# Revised.net
KiCad netlist of a schematic drawn in EAGLE
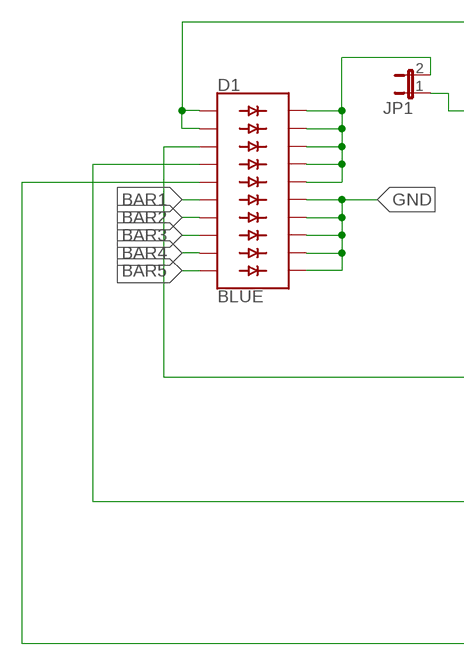
[diagram p0: schematic, sheet 1, part 1 of 2]
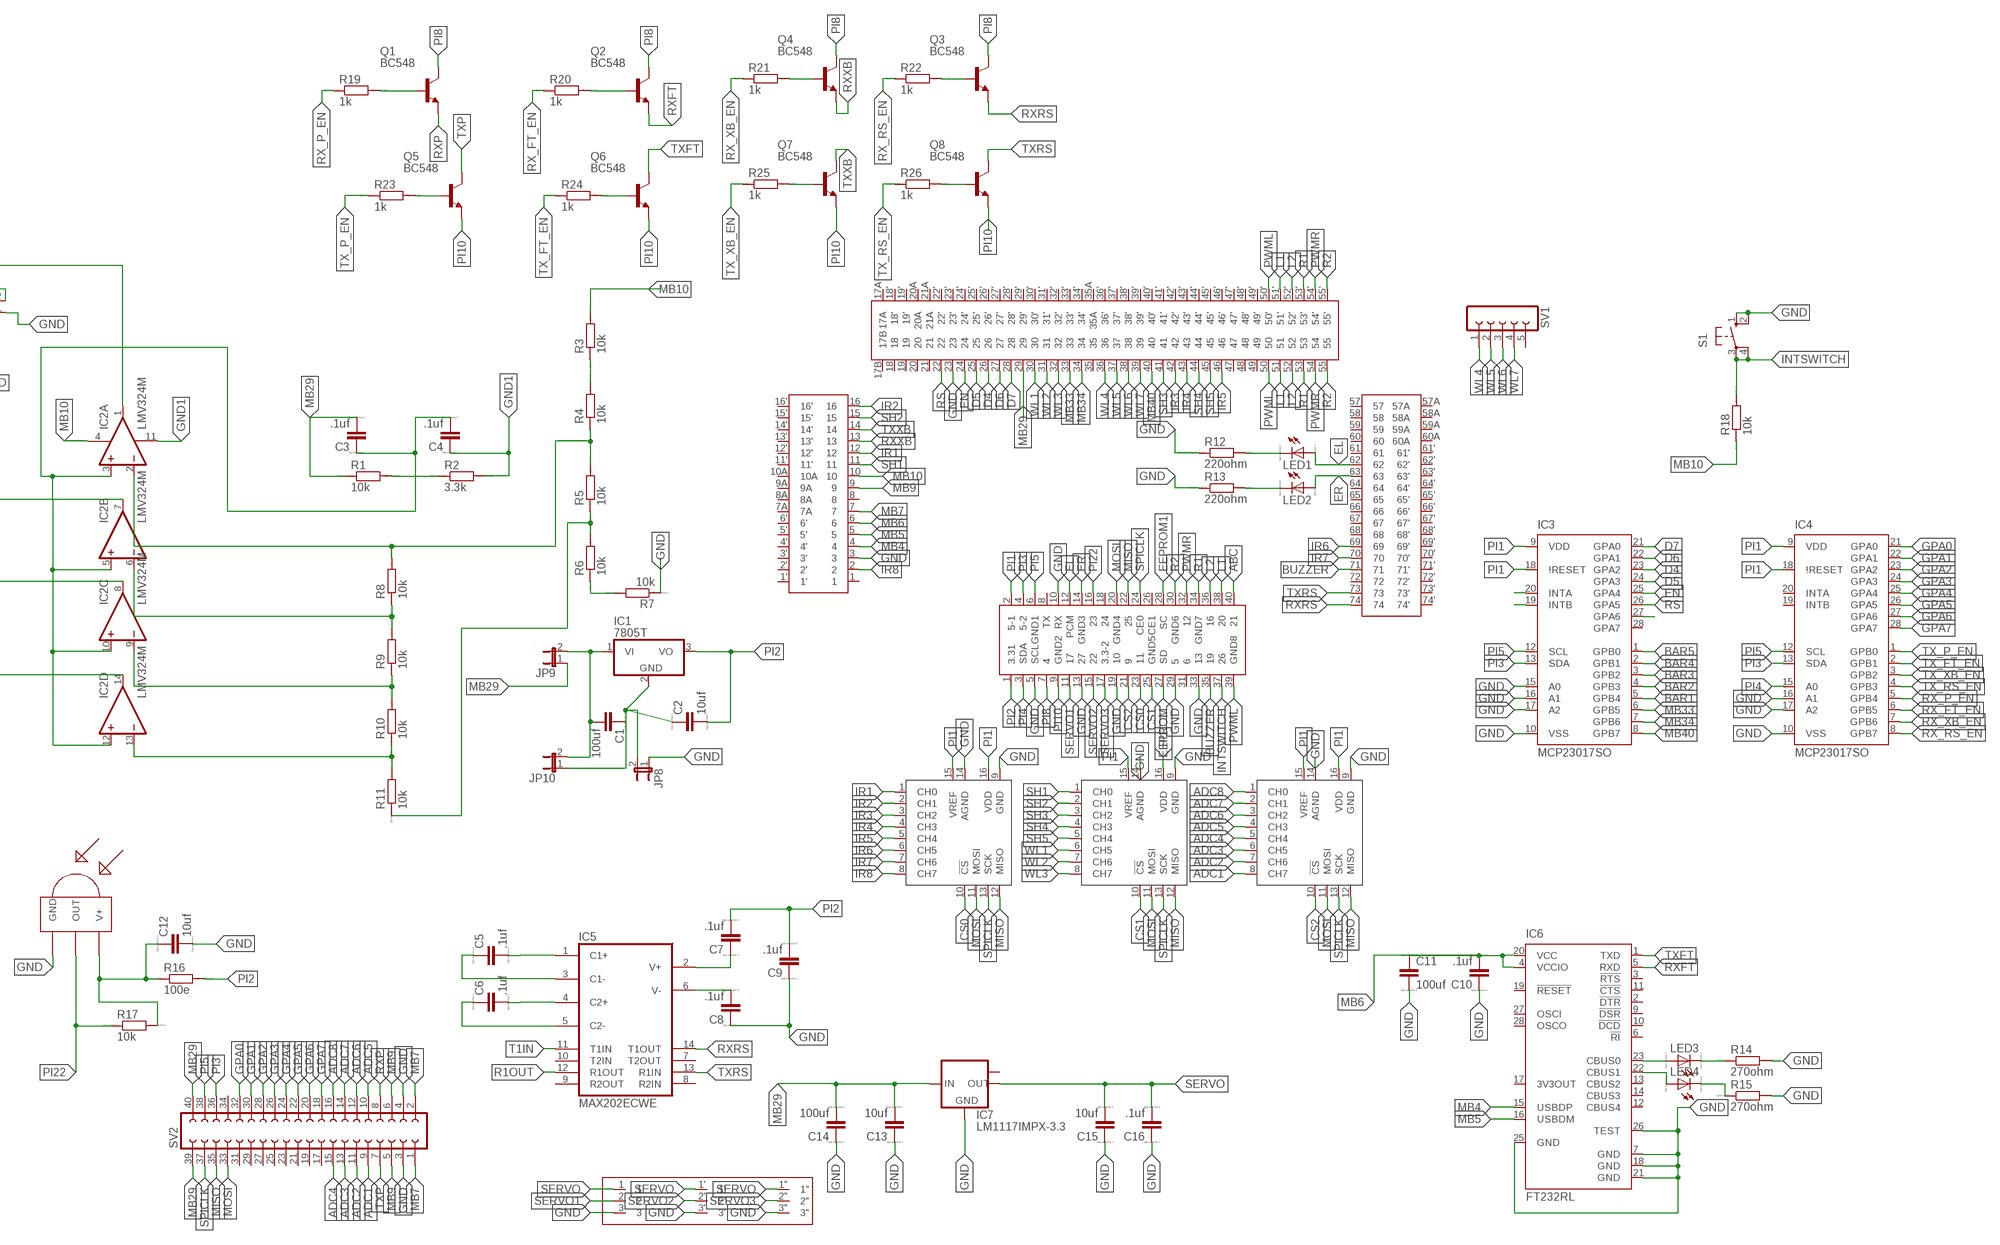
[diagram p1: schematic, sheet 1, part 2 of 2]

(export (version "E")
  (design (tool "Eeschema 10.0.6"))
  (components
    (comp (ref "C1")
      (value "100uf")
      (footprint "eagle-import:C1206")
      (libsource (lib "eagle-import") (part "CC1206"))
    )
    (comp (ref "C2")
      (value "10uf")
      (footprint "eagle-import:C1206")
      (libsource (lib "eagle-import") (part "CC1206"))
    )
    (comp (ref "C3")
      (value ".1uf")
      (footprint "eagle-import:C1206")
      (libsource (lib "eagle-import") (part "CC1206"))
    )
    (comp (ref "C4")
      (value ".1uf")
      (footprint "eagle-import:C1206")
      (libsource (lib "eagle-import") (part "CC1206"))
    )
    (comp (ref "C5")
      (value ".1uf")
      (footprint "eagle-import:C1206")
      (libsource (lib "eagle-import") (part "CC1206"))
    )
    (comp (ref "C6")
      (value ".1uf")
      (footprint "eagle-import:C1206")
      (libsource (lib "eagle-import") (part "CC1206"))
    )
    (comp (ref "C7")
      (value ".1uf")
      (footprint "eagle-import:C1206")
      (libsource (lib "eagle-import") (part "CC1206"))
    )
    (comp (ref "C8")
      (value ".1uf")
      (footprint "eagle-import:C1206")
      (libsource (lib "eagle-import") (part "CC1206"))
    )
    (comp (ref "C9")
      (value ".1uf")
      (footprint "eagle-import:C1206")
      (libsource (lib "eagle-import") (part "CC1206"))
    )
    (comp (ref "C10")
      (value ".1uf")
      (footprint "eagle-import:C1206")
      (libsource (lib "eagle-import") (part "CC1206"))
    )
    (comp (ref "C11")
      (value "100uf")
      (footprint "eagle-import:C1206")
      (libsource (lib "eagle-import") (part "CC1206"))
    )
    (comp (ref "C12")
      (value "10uf")
      (footprint "eagle-import:C1206")
      (libsource (lib "eagle-import") (part "CC1206"))
    )
    (comp (ref "C13")
      (value "10uf")
      (footprint "eagle-import:C1206")
      (libsource (lib "eagle-import") (part "CC1206"))
    )
    (comp (ref "C14")
      (value "100uf")
      (footprint "eagle-import:C1206")
      (libsource (lib "eagle-import") (part "CC1206"))
    )
    (comp (ref "C15")
      (value "10uf")
      (footprint "eagle-import:C1206")
      (libsource (lib "eagle-import") (part "CC1206"))
    )
    (comp (ref "C16")
      (value ".1uf")
      (footprint "eagle-import:C1206")
      (libsource (lib "eagle-import") (part "CC1206"))
    )
    (comp (ref "D1")
      (value "BLUE")
      (footprint "eagle-import:LED_BARGRAPH_10")
      (libsource (lib "eagle-import") (part "LED_BARGRAPH_10BLUE"))
    )
    (comp (ref "IC1")
      (value "7805T")
      (footprint "eagle-import:TO220H")
      (libsource (lib "eagle-import") (part "78T05"))
    )
    (comp (ref "IC2")
      (value "LMV324M")
      (footprint "eagle-import:SO14")
      (libsource (lib "eagle-import") (part "LMV324?M"))
    )
    (comp (ref "IC3")
      (value "MCP23017SO")
      (footprint "eagle-import:SO28W")
      (libsource (lib "eagle-import") (part "MCP23017SO"))
    )
    (comp (ref "IC4")
      (value "MCP23017SO")
      (footprint "eagle-import:SO28W")
      (libsource (lib "eagle-import") (part "MCP23017SO"))
    )
    (comp (ref "IC5")
      (value "MAX202ECWE")
      (footprint "eagle-import:SO16L")
      (fields (field (name "MPN") "MAX202ECWE+T"))
      (libsource (lib "eagle-import") (part "MAX202ECWE"))
    )
    (comp (ref "IC6")
      (value "FT232RL")
      (footprint "eagle-import:SSOP28")
      (libsource (lib "eagle-import") (part "FT232RL"))
    )
    (comp (ref "IC7")
      (value "LM1117IMPX-3.3")
      (footprint "eagle-import:SOT223")
      (libsource (lib "eagle-import") (part "LM1117IMPX-3.3"))
    )
    (comp (ref "JP1")
      (value "JP1E")
      (footprint "eagle-import:JP1")
      (libsource (lib "eagle-import") (part "JP1E"))
    )
    (comp (ref "JP8")
      (value "JP1E")
      (footprint "eagle-import:JP1")
      (libsource (lib "eagle-import") (part "JP1E"))
    )
    (comp (ref "JP9")
      (value "JP1E")
      (footprint "eagle-import:JP1")
      (libsource (lib "eagle-import") (part "JP1E"))
    )
    (comp (ref "JP10")
      (value "JP1E")
      (footprint "eagle-import:JP1")
      (libsource (lib "eagle-import") (part "JP1E"))
    )
    (comp (ref "LED1")
      (value "LED_E")
      (footprint "eagle-import:LED_1206")
      (libsource (lib "eagle-import") (part "LED_E"))
    )
    (comp (ref "LED2")
      (value "LED_E")
      (footprint "eagle-import:LED_1206")
      (libsource (lib "eagle-import") (part "LED_E"))
    )
    (comp (ref "LED3")
      (value "LED_E")
      (footprint "eagle-import:LED_1206")
      (libsource (lib "eagle-import") (part "LED_E"))
    )
    (comp (ref "LED4")
      (value "LED_E")
      (footprint "eagle-import:LED_1206")
      (libsource (lib "eagle-import") (part "LED_E"))
    )
    (comp (ref "Q1")
      (value "BC548")
      (footprint "eagle-import:TO92-EBC")
      (libsource (lib "eagle-import") (part "BC548"))
    )
    (comp (ref "Q2")
      (value "BC548")
      (footprint "eagle-import:TO92-EBC")
      (libsource (lib "eagle-import") (part "BC548"))
    )
    (comp (ref "Q3")
      (value "BC548")
      (footprint "eagle-import:TO92-EBC")
      (libsource (lib "eagle-import") (part "BC548"))
    )
    (comp (ref "Q4")
      (value "BC548")
      (footprint "eagle-import:TO92-EBC")
      (libsource (lib "eagle-import") (part "BC548"))
    )
    (comp (ref "Q5")
      (value "BC548")
      (footprint "eagle-import:TO92-EBC")
      (libsource (lib "eagle-import") (part "BC548"))
    )
    (comp (ref "Q6")
      (value "BC548")
      (footprint "eagle-import:TO92-EBC")
      (libsource (lib "eagle-import") (part "BC548"))
    )
    (comp (ref "Q7")
      (value "BC548")
      (footprint "eagle-import:TO92-EBC")
      (libsource (lib "eagle-import") (part "BC548"))
    )
    (comp (ref "Q8")
      (value "BC548")
      (footprint "eagle-import:TO92-EBC")
      (libsource (lib "eagle-import") (part "BC548"))
    )
    (comp (ref "R1")
      (value "10k")
      (footprint "eagle-import:R1206")
      (libsource (lib "eagle-import") (part "RR1206"))
    )
    (comp (ref "R2")
      (value "3.3k")
      (footprint "eagle-import:R1206")
      (libsource (lib "eagle-import") (part "RR1206"))
    )
    (comp (ref "R3")
      (value "10k")
      (footprint "eagle-import:R1206")
      (libsource (lib "eagle-import") (part "RR1206"))
    )
    (comp (ref "R4")
      (value "10k")
      (footprint "eagle-import:R1206")
      (libsource (lib "eagle-import") (part "RR1206"))
    )
    (comp (ref "R5")
      (value "10k")
      (footprint "eagle-import:R1206")
      (libsource (lib "eagle-import") (part "RR1206"))
    )
    (comp (ref "R6")
      (value "10k")
      (footprint "eagle-import:R1206")
      (libsource (lib "eagle-import") (part "RR1206"))
    )
    (comp (ref "R7")
      (value "10k")
      (footprint "eagle-import:R1206")
      (libsource (lib "eagle-import") (part "RR1206"))
    )
    (comp (ref "R8")
      (value "10k")
      (footprint "eagle-import:R1206")
      (libsource (lib "eagle-import") (part "RR1206"))
    )
    (comp (ref "R9")
      (value "10k")
      (footprint "eagle-import:R1206")
      (libsource (lib "eagle-import") (part "RR1206"))
    )
    (comp (ref "R10")
      (value "10k")
      (footprint "eagle-import:R1206")
      (libsource (lib "eagle-import") (part "RR1206"))
    )
    (comp (ref "R11")
      (value "10k")
      (footprint "eagle-import:R1206")
      (libsource (lib "eagle-import") (part "RR1206"))
    )
    (comp (ref "R12")
      (value "220ohm")
      (footprint "eagle-import:R1206")
      (libsource (lib "eagle-import") (part "RR1206"))
    )
    (comp (ref "R13")
      (value "220ohm")
      (footprint "eagle-import:R1206")
      (libsource (lib "eagle-import") (part "RR1206"))
    )
    (comp (ref "R14")
      (value "270ohm")
      (footprint "eagle-import:R1206")
      (libsource (lib "eagle-import") (part "RR1206"))
    )
    (comp (ref "R15")
      (value "270ohm")
      (footprint "eagle-import:R1206")
      (libsource (lib "eagle-import") (part "RR1206"))
    )
    (comp (ref "R16")
      (value "100e")
      (footprint "eagle-import:R1206")
      (libsource (lib "eagle-import") (part "RR1206"))
    )
    (comp (ref "R17")
      (value "10k")
      (footprint "eagle-import:R1206")
      (libsource (lib "eagle-import") (part "RR1206"))
    )
    (comp (ref "R18")
      (value "10k")
      (footprint "eagle-import:R1206")
      (libsource (lib "eagle-import") (part "RR1206"))
    )
    (comp (ref "R19")
      (value "1k")
      (footprint "eagle-import:R1206")
      (libsource (lib "eagle-import") (part "RR1206"))
    )
    (comp (ref "R20")
      (value "1k")
      (footprint "eagle-import:R1206")
      (libsource (lib "eagle-import") (part "RR1206"))
    )
    (comp (ref "R21")
      (value "1k")
      (footprint "eagle-import:R1206")
      (libsource (lib "eagle-import") (part "RR1206"))
    )
    (comp (ref "R22")
      (value "1k")
      (footprint "eagle-import:R1206")
      (libsource (lib "eagle-import") (part "RR1206"))
    )
    (comp (ref "R23")
      (value "1k")
      (footprint "eagle-import:R1206")
      (libsource (lib "eagle-import") (part "RR1206"))
    )
    (comp (ref "R24")
      (value "1k")
      (footprint "eagle-import:R1206")
      (libsource (lib "eagle-import") (part "RR1206"))
    )
    (comp (ref "R25")
      (value "1k")
      (footprint "eagle-import:R1206")
      (libsource (lib "eagle-import") (part "RR1206"))
    )
    (comp (ref "R26")
      (value "1k")
      (footprint "eagle-import:R1206")
      (libsource (lib "eagle-import") (part "RR1206"))
    )
    (comp (ref "S1")
      (value "10-XX")
      (footprint "eagle-import:B3F-10XX")
      (fields (field (name "MPN") "B3F-1000"))
      (libsource (lib "eagle-import") (part "10-XX"))
    )
    (comp (ref "SV1")
      (value "FE05-1")
      (footprint "eagle-import:FE05-1")
      (libsource (lib "eagle-import") (part "FE05-1"))
    )
    (comp (ref "SV2")
      (value "FE20-2")
      (footprint "eagle-import:FE20-2")
      (libsource (lib "eagle-import") (part "FE20-2"))
    )
    (comp (ref "U$1")
      (value "DAUGHTERBOARDDAUGHTERBOARD")
      (footprint "eagle-import:DAUGHTERBOARD")
      (libsource (lib "eagle-import") (part "DAUGHTERBOARDDAUGHTERBOARD"))
    )
    (comp (ref "U$2")
      (value "MALE_HEADER")
      (footprint "eagle-import:MALE_HEADER_PACKAGE")
      (libsource (lib "eagle-import") (part "MALE_HEADER"))
    )
    (comp (ref "U$3")
      (value "MCP3008SL")
      (footprint "eagle-import:SO16")
      (libsource (lib "eagle-import") (part "MCP3008SL"))
    )
    (comp (ref "U$4")
      (value "MCP3008SL")
      (footprint "eagle-import:SO16")
      (libsource (lib "eagle-import") (part "MCP3008SL"))
    )
    (comp (ref "U$5")
      (value "MCP3008SL")
      (footprint "eagle-import:SO16")
      (libsource (lib "eagle-import") (part "MCP3008SL"))
    )
    (comp (ref "U$6")
      (value "TSOP1738")
      (footprint "eagle-import:TSOP17XX")
      (libsource (lib "eagle-import") (part "TSOP1738"))
    )
    (comp (ref "U$7")
      (value "SERVO")
      (footprint "eagle-import:SERVO")
      (libsource (lib "eagle-import") (part "SERVO"))
    )
  )
  (nets
    (net (code "1") (name "ABC") (class "Default")
      (node (ref "U$2") (pin "40") (pinfunction "21_40") (pintype "bidirectional"))
    )
    (net (code "2") (name "ADC1") (class "Default")
      (node (ref "SV2") (pin "9") (pinfunction "9_9") (pintype "passive"))
      (node (ref "U$5") (pin "8") (pinfunction "CH7_8") (pintype "input"))
    )
    (net (code "3") (name "ADC2") (class "Default")
      (node (ref "SV2") (pin "11") (pinfunction "11_11") (pintype "passive"))
      (node (ref "U$5") (pin "7") (pinfunction "CH6_7") (pintype "input"))
    )
    (net (code "4") (name "ADC3") (class "Default")
      (node (ref "SV2") (pin "13") (pinfunction "13_13") (pintype "passive"))
      (node (ref "U$5") (pin "6") (pinfunction "CH5_6") (pintype "input"))
    )
    (net (code "5") (name "ADC4") (class "Default")
      (node (ref "SV2") (pin "15") (pinfunction "15_15") (pintype "passive"))
      (node (ref "U$5") (pin "5") (pinfunction "CH4_5") (pintype "input"))
    )
    (net (code "6") (name "ADC5") (class "Default")
      (node (ref "SV2") (pin "10") (pinfunction "10_10") (pintype "passive"))
      (node (ref "U$5") (pin "4") (pinfunction "CH3_4") (pintype "input"))
    )
    (net (code "7") (name "ADC6") (class "Default")
      (node (ref "SV2") (pin "12") (pinfunction "12_12") (pintype "passive"))
      (node (ref "U$5") (pin "3") (pinfunction "CH2_3") (pintype "input"))
    )
    (net (code "8") (name "ADC7") (class "Default")
      (node (ref "SV2") (pin "14") (pinfunction "14_14") (pintype "passive"))
      (node (ref "U$5") (pin "2") (pinfunction "CH1_2") (pintype "input"))
    )
    (net (code "9") (name "ADC8") (class "Default")
      (node (ref "SV2") (pin "16") (pinfunction "16_16") (pintype "passive"))
      (node (ref "U$5") (pin "1") (pinfunction "CH0_1") (pintype "input"))
    )
    (net (code "10") (name "BAR1") (class "Default")
      (node (ref "D1") (pin "6") (pinfunction "A5_6") (pintype "passive"))
      (node (ref "IC3") (pin "5") (pinfunction "GPB4_5") (pintype "bidirectional"))
    )
    (net (code "11") (name "BAR2") (class "Default")
      (node (ref "D1") (pin "7") (pinfunction "A6_7") (pintype "passive"))
      (node (ref "IC3") (pin "4") (pinfunction "GPB3_4") (pintype "bidirectional"))
    )
    (net (code "12") (name "BAR3") (class "Default")
      (node (ref "D1") (pin "8") (pinfunction "A7_8") (pintype "passive"))
      (node (ref "IC3") (pin "3") (pinfunction "GPB2_3") (pintype "bidirectional"))
    )
    (net (code "13") (name "BAR4") (class "Default")
      (node (ref "D1") (pin "9") (pinfunction "A8_9") (pintype "passive"))
      (node (ref "IC3") (pin "2") (pinfunction "GPB1_2") (pintype "bidirectional"))
    )
    (net (code "14") (name "BAR5") (class "Default")
      (node (ref "D1") (pin "10") (pinfunction "A9_10") (pintype "passive"))
      (node (ref "IC3") (pin "1") (pinfunction "GPB0_1") (pintype "bidirectional"))
    )
    (net (code "15") (name "BUZZER") (class "Default")
      (node (ref "U$1") (pin "71") (pinfunction "71_71") (pintype "output"))
      (node (ref "U$2") (pin "35") (pinfunction "19_35") (pintype "bidirectional"))
    )
    (net (code "16") (name "CS0") (class "Default")
      (node (ref "U$2") (pin "23") (pinfunction "11_23") (pintype "bidirectional"))
      (node (ref "U$3") (pin "10") (pinfunction "~{CS}_10") (pintype "input"))
    )
    (net (code "17") (name "CS1") (class "Default")
      (node (ref "U$2") (pin "25") (pinfunction "GND5_25") (pintype "bidirectional"))
      (node (ref "U$4") (pin "10") (pinfunction "~{CS}_10") (pintype "input"))
    )
    (net (code "18") (name "CS2") (class "Default")
      (node (ref "U$2") (pin "21") (pinfunction "9_21") (pintype "bidirectional"))
      (node (ref "U$5") (pin "10") (pinfunction "~{CS}_10") (pintype "input"))
    )
    (net (code "19") (name "D4") (class "Default")
      (node (ref "IC3") (pin "23") (pinfunction "GPA2_23") (pintype "bidirectional"))
      (node (ref "U$1") (pin "26") (pinfunction "26_26") (pintype "output"))
    )
    (net (code "20") (name "D5") (class "Default")
      (node (ref "IC3") (pin "24") (pinfunction "GPA3_24") (pintype "bidirectional"))
      (node (ref "U$1") (pin "25") (pinfunction "25_25") (pintype "output"))
    )
    (net (code "21") (name "D6") (class "Default")
      (node (ref "IC3") (pin "22") (pinfunction "GPA1_22") (pintype "bidirectional"))
      (node (ref "U$1") (pin "27") (pinfunction "27_27") (pintype "output"))
    )
    (net (code "22") (name "D7") (class "Default")
      (node (ref "IC3") (pin "21") (pinfunction "GPA0_21") (pintype "bidirectional"))
      (node (ref "U$1") (pin "28") (pinfunction "28_28") (pintype "output"))
    )
    (net (code "23") (name "EEPROM") (class "Default")
      (node (ref "U$2") (pin "27") (pinfunction "SD_27") (pintype "bidirectional"))
    )
    (net (code "24") (name "EEPROM1") (class "Default")
      (node (ref "U$2") (pin "28") (pinfunction "SC_28") (pintype "bidirectional"))
    )
    (net (code "25") (name "EL") (class "Default")
      (node (ref "LED1") (pin "A") (pinfunction "A_A") (pintype "passive"))
      (node (ref "U$1") (pin "62") (pinfunction "62_62") (pintype "output"))
      (node (ref "U$2") (pin "12") (pinfunction "PCM_12") (pintype "bidirectional"))
    )
    (net (code "26") (name "EN") (class "Default")
      (node (ref "IC3") (pin "25") (pinfunction "GPA4_25") (pintype "bidirectional"))
      (node (ref "U$1") (pin "24") (pinfunction "24_24") (pintype "output"))
    )
    (net (code "27") (name "ER") (class "Default")
      (node (ref "LED2") (pin "A") (pinfunction "A_A") (pintype "passive"))
      (node (ref "U$1") (pin "63") (pinfunction "63_63") (pintype "output"))
      (node (ref "U$2") (pin "14") (pinfunction "GND3_14") (pintype "bidirectional"))
    )
    (net (code "28") (name "GND") (class "Default")
      (node (ref "C10") (pin "1") (pinfunction "1_1") (pintype "passive"))
      (node (ref "C11") (pin "2") (pinfunction "2_2") (pintype "passive"))
      (node (ref "C12") (pin "2") (pinfunction "2_2") (pintype "passive"))
      (node (ref "C13") (pin "1") (pinfunction "1_1") (pintype "passive"))
      (node (ref "C14") (pin "1") (pinfunction "1_1") (pintype "passive"))
      (node (ref "C15") (pin "1") (pinfunction "1_1") (pintype "passive"))
      (node (ref "C16") (pin "1") (pinfunction "1_1") (pintype "passive"))
      (node (ref "C8") (pin "1") (pinfunction "1_1") (pintype "passive"))
      (node (ref "C9") (pin "1") (pinfunction "1_1") (pintype "passive"))
      (node (ref "D1") (pin "11") (pinfunction "C9_11") (pintype "passive"))
      (node (ref "D1") (pin "12") (pinfunction "C8_12") (pintype "passive"))
      (node (ref "D1") (pin "13") (pinfunction "C7_13") (pintype "passive"))
      (node (ref "D1") (pin "14") (pinfunction "C6_14") (pintype "passive"))
      (node (ref "D1") (pin "15") (pinfunction "C5_15") (pintype "passive"))
      (node (ref "IC3") (pin "10") (pinfunction "VSS_10") (pintype "power_in"))
      (node (ref "IC3") (pin "15") (pinfunction "A0_15") (pintype "input"))
      (node (ref "IC3") (pin "16") (pinfunction "A1_16") (pintype "input"))
      (node (ref "IC3") (pin "17") (pinfunction "A2_17") (pintype "input"))
      (node (ref "IC4") (pin "10") (pinfunction "VSS_10") (pintype "power_in"))
      (node (ref "IC4") (pin "16") (pinfunction "A1_16") (pintype "input"))
      (node (ref "IC4") (pin "17") (pinfunction "A2_17") (pintype "input"))
      (node (ref "IC6") (pin "18") (pinfunction "GND_18") (pintype "power_in"))
      (node (ref "IC6") (pin "21") (pinfunction "GND_21") (pintype "power_in"))
      (node (ref "IC6") (pin "25") (pinfunction "GND_25") (pintype "power_in"))
      (node (ref "IC6") (pin "26") (pinfunction "TEST_26") (pintype "input"))
      (node (ref "IC6") (pin "7") (pinfunction "GND_7") (pintype "power_in"))
      (node (ref "IC7") (pin "1") (pinfunction "GND_1") (pintype "input"))
      (node (ref "JP1") (pin "1") (pinfunction "1_1") (pintype "passive"))
      (node (ref "JP8") (pin "1") (pinfunction "1_1") (pintype "passive"))
      (node (ref "R12") (pin "1") (pinfunction "1_1") (pintype "passive"))
      (node (ref "R13") (pin "1") (pinfunction "1_1") (pintype "passive"))
      (node (ref "R14") (pin "2") (pinfunction "2_2") (pintype "passive"))
      (node (ref "R15") (pin "2") (pinfunction "2_2") (pintype "passive"))
      (node (ref "R7") (pin "1") (pinfunction "1_1") (pintype "passive"))
      (node (ref "S1") (pin "1") (pinfunction "S_1") (pintype "passive"))
      (node (ref "S1") (pin "2") (pinfunction "S1_2") (pintype "passive"))
      (node (ref "SV2") (pin "3") (pinfunction "3_3") (pintype "passive"))
      (node (ref "SV2") (pin "4") (pinfunction "4_4") (pintype "passive"))
      (node (ref "U$1") (pin "23") (pinfunction "23_23") (pintype "output"))
      (node (ref "U$1") (pin "3") (pinfunction "3_3") (pintype "output"))
      (node (ref "U$2") (pin "10") (pinfunction "RX_10") (pintype "bidirectional"))
      (node (ref "U$2") (pin "13") (pinfunction "27_13") (pintype "bidirectional"))
      (node (ref "U$2") (pin "19") (pinfunction "10_19") (pintype "bidirectional"))
      (node (ref "U$2") (pin "29") (pinfunction "5_29") (pintype "bidirectional"))
      (node (ref "U$2") (pin "33") (pinfunction "13_33") (pintype "bidirectional"))
      (node (ref "U$2") (pin "5") (pinfunction "SCL_5") (pintype "bidirectional"))
      (node (ref "U$3") (pin "14") (pinfunction "AGND_14") (pintype "power_in"))
      (node (ref "U$3") (pin "9") (pinfunction "GND_9") (pintype "power_in"))
      (node (ref "U$4") (pin "14") (pinfunction "AGND_14") (pintype "power_in"))
      (node (ref "U$4") (pin "9") (pinfunction "GND_9") (pintype "power_in"))
      (node (ref "U$5") (pin "14") (pinfunction "AGND_14") (pintype "power_in"))
      (node (ref "U$5") (pin "9") (pinfunction "GND_9") (pintype "power_in"))
      (node (ref "U$6") (pin "GND") (pinfunction "GND_GND") (pintype "bidirectional"))
      (node (ref "U$7") (pin "3") (pinfunction "3_3") (pintype "bidirectional"))
      (node (ref "U$7") (pin "3\"") (pinfunction "3\"_3\"") (pintype "bidirectional"))
      (node (ref "U$7") (pin "3'") (pinfunction "3'_3'") (pintype "bidirectional"))
    )
    (net (code "29") (name "GND1") (class "Default")
      (node (ref "C4") (pin "1") (pinfunction "1_1") (pintype "passive"))
      (node (ref "IC2") (pin "11") (pinfunction "V-_11") (pintype "power_in"))
      (node (ref "R2") (pin "2") (pinfunction "2_2") (pintype "passive"))
    )
    (net (code "30") (name "GPA0") (class "Default")
      (node (ref "IC4") (pin "21") (pinfunction "GPA0_21") (pintype "bidirectional"))
      (node (ref "SV2") (pin "32") (pinfunction "32_32") (pintype "passive"))
    )
    (net (code "31") (name "GPA1") (class "Default")
      (node (ref "IC4") (pin "22") (pinfunction "GPA1_22") (pintype "bidirectional"))
      (node (ref "SV2") (pin "30") (pinfunction "30_30") (pintype "passive"))
    )
    (net (code "32") (name "GPA2") (class "Default")
      (node (ref "IC4") (pin "23") (pinfunction "GPA2_23") (pintype "bidirectional"))
      (node (ref "SV2") (pin "28") (pinfunction "28_28") (pintype "passive"))
    )
    (net (code "33") (name "GPA3") (class "Default")
      (node (ref "IC4") (pin "24") (pinfunction "GPA3_24") (pintype "bidirectional"))
      (node (ref "SV2") (pin "26") (pinfunction "26_26") (pintype "passive"))
    )
    (net (code "34") (name "GPA4") (class "Default")
      (node (ref "IC4") (pin "25") (pinfunction "GPA4_25") (pintype "bidirectional"))
      (node (ref "SV2") (pin "24") (pinfunction "24_24") (pintype "passive"))
    )
    (net (code "35") (name "GPA5") (class "Default")
      (node (ref "IC4") (pin "26") (pinfunction "GPA5_26") (pintype "bidirectional"))
      (node (ref "SV2") (pin "22") (pinfunction "22_22") (pintype "passive"))
    )
    (net (code "36") (name "GPA6") (class "Default")
      (node (ref "IC4") (pin "27") (pinfunction "GPA6_27") (pintype "bidirectional"))
      (node (ref "SV2") (pin "20") (pinfunction "20_20") (pintype "passive"))
    )
    (net (code "37") (name "GPA7") (class "Default")
      (node (ref "IC4") (pin "28") (pinfunction "GPA7_28") (pintype "bidirectional"))
      (node (ref "SV2") (pin "18") (pinfunction "18_18") (pintype "passive"))
    )
    (net (code "38") (name "INTSWITCH") (class "Default")
      (node (ref "R18") (pin "2") (pinfunction "2_2") (pintype "passive"))
      (node (ref "S1") (pin "3") (pinfunction "P_3") (pintype "passive"))
      (node (ref "S1") (pin "4") (pinfunction "P1_4") (pintype "passive"))
      (node (ref "U$2") (pin "37") (pinfunction "26_37") (pintype "bidirectional"))
    )
    (net (code "39") (name "IR1") (class "Default")
      (node (ref "U$1") (pin "12") (pinfunction "12_12") (pintype "output"))
      (node (ref "U$3") (pin "1") (pinfunction "CH0_1") (pintype "input"))
    )
    (net (code "40") (name "IR2") (class "Default")
      (node (ref "U$1") (pin "16") (pinfunction "16_16") (pintype "output"))
      (node (ref "U$3") (pin "2") (pinfunction "CH1_2") (pintype "input"))
    )
    (net (code "41") (name "IR3") (class "Default")
      (node (ref "U$1") (pin "42") (pinfunction "42_42") (pintype "output"))
      (node (ref "U$3") (pin "3") (pinfunction "CH2_3") (pintype "input"))
    )
    (net (code "42") (name "IR4") (class "Default")
      (node (ref "U$1") (pin "43") (pinfunction "43_43") (pintype "output"))
      (node (ref "U$3") (pin "4") (pinfunction "CH3_4") (pintype "input"))
    )
    (net (code "43") (name "IR5") (class "Default")
      (node (ref "U$1") (pin "46") (pinfunction "46_46") (pintype "output"))
      (node (ref "U$3") (pin "5") (pinfunction "CH4_5") (pintype "input"))
    )
    (net (code "44") (name "IR6") (class "Default")
      (node (ref "U$1") (pin "69") (pinfunction "69_69") (pintype "output"))
      (node (ref "U$3") (pin "6") (pinfunction "CH5_6") (pintype "input"))
    )
    (net (code "45") (name "IR7") (class "Default")
      (node (ref "U$1") (pin "70") (pinfunction "70_70") (pintype "output"))
      (node (ref "U$3") (pin "7") (pinfunction "CH6_7") (pintype "input"))
    )
    (net (code "46") (name "IR8") (class "Default")
      (node (ref "U$1") (pin "2") (pinfunction "2_2") (pintype "output"))
      (node (ref "U$3") (pin "8") (pinfunction "CH7_8") (pintype "input"))
    )
    (net (code "47") (name "L1") (class "Default")
      (node (ref "U$1") (pin "51") (pinfunction "51_51") (pintype "output"))
      (node (ref "U$1") (pin "51'") (pinfunction "51'_51'") (pintype "output"))
      (node (ref "U$2") (pin "38") (pinfunction "20_38") (pintype "bidirectional"))
    )
    (net (code "48") (name "L2") (class "Default")
      (node (ref "U$1") (pin "52") (pinfunction "52_52") (pintype "output"))
      (node (ref "U$1") (pin "52'") (pinfunction "52'_52'") (pintype "output"))
      (node (ref "U$2") (pin "36") (pinfunction "16_36") (pintype "bidirectional"))
    )
    (net (code "49") (name "MB4") (class "Default")
      (node (ref "IC6") (pin "15") (pinfunction "USBDP_15") (pintype "bidirectional"))
      (node (ref "U$1") (pin "4") (pinfunction "4_4") (pintype "output"))
    )
    (net (code "50") (name "MB5") (class "Default")
      (node (ref "IC6") (pin "16") (pinfunction "USBDM_16") (pintype "bidirectional"))
      (node (ref "U$1") (pin "5") (pinfunction "5_5") (pintype "output"))
    )
    (net (code "51") (name "MB6") (class "Default")
      (node (ref "C10") (pin "2") (pinfunction "2_2") (pintype "passive"))
      (node (ref "C11") (pin "1") (pinfunction "1_1") (pintype "passive"))
      (node (ref "IC6") (pin "20") (pinfunction "VCC_20") (pintype "power_in"))
      (node (ref "IC6") (pin "4") (pinfunction "VCCIO_4") (pintype "power_in"))
      (node (ref "U$1") (pin "6") (pinfunction "6_6") (pintype "output"))
    )
    (net (code "52") (name "MB7") (class "Default")
      (node (ref "SV2") (pin "1") (pinfunction "1_1") (pintype "passive"))
      (node (ref "SV2") (pin "2") (pinfunction "2_2") (pintype "passive"))
      (node (ref "U$1") (pin "7") (pinfunction "7_7") (pintype "output"))
    )
    (net (code "53") (name "MB9") (class "Default")
      (node (ref "SV2") (pin "5") (pinfunction "5_5") (pintype "passive"))
      (node (ref "SV2") (pin "6") (pinfunction "6_6") (pintype "passive"))
      (node (ref "U$1") (pin "9") (pinfunction "9_9") (pintype "output"))
    )
    (net (code "54") (name "MB10") (class "Default")
      (node (ref "IC2") (pin "4") (pinfunction "V+_4") (pintype "power_in"))
      (node (ref "R18") (pin "1") (pinfunction "1_1") (pintype "passive"))
      (node (ref "R3") (pin "2") (pinfunction "2_2") (pintype "passive"))
      (node (ref "U$1") (pin "10") (pinfunction "10_10") (pintype "output"))
    )
    (net (code "55") (name "MB29") (class "Default")
      (node (ref "C13") (pin "2") (pinfunction "2_2") (pintype "passive"))
      (node (ref "C14") (pin "2") (pinfunction "2_2") (pintype "passive"))
      (node (ref "C3") (pin "2") (pinfunction "2_2") (pintype "passive"))
      (node (ref "IC7") (pin "3") (pinfunction "IN_3") (pintype "input"))
      (node (ref "JP9") (pin "1") (pinfunction "1_1") (pintype "passive"))
      (node (ref "R1") (pin "1") (pinfunction "1_1") (pintype "passive"))
      (node (ref "SV2") (pin "39") (pinfunction "39_39") (pintype "passive"))
      (node (ref "SV2") (pin "40") (pinfunction "40_40") (pintype "passive"))
      (node (ref "U$1") (pin "29") (pinfunction "29_29") (pintype "output"))
    )
    (net (code "56") (name "MB33") (class "Default")
      (node (ref "IC3") (pin "6") (pinfunction "GPB5_6") (pintype "bidirectional"))
      (node (ref "U$1") (pin "33") (pinfunction "33_33") (pintype "output"))
    )
    (net (code "57") (name "MB34") (class "Default")
      (node (ref "IC3") (pin "7") (pinfunction "GPB6_7") (pintype "bidirectional"))
      (node (ref "U$1") (pin "34") (pinfunction "34_34") (pintype "output"))
    )
    (net (code "58") (name "MB40") (class "Default")
      (node (ref "IC3") (pin "8") (pinfunction "GPB7_8") (pintype "bidirectional"))
      (node (ref "U$1") (pin "40") (pinfunction "40_40") (pintype "output"))
    )
    (net (code "59") (name "MISO") (class "Default")
      (node (ref "SV2") (pin "35") (pinfunction "35_35") (pintype "passive"))
      (node (ref "U$2") (pin "22") (pinfunction "25_22") (pintype "bidirectional"))
      (node (ref "U$3") (pin "12") (pinfunction "MISO_12") (pintype "output"))
      (node (ref "U$4") (pin "12") (pinfunction "MISO_12") (pintype "output"))
      (node (ref "U$5") (pin "12") (pinfunction "MISO_12") (pintype "output"))
    )
    (net (code "60") (name "MOSI") (class "Default")
      (node (ref "SV2") (pin "33") (pinfunction "33_33") (pintype "passive"))
      (node (ref "U$2") (pin "20") (pinfunction "GND4_20") (pintype "bidirectional"))
      (node (ref "U$3") (pin "11") (pinfunction "MOSI_11") (pintype "input"))
      (node (ref "U$4") (pin "11") (pinfunction "MOSI_11") (pintype "input"))
      (node (ref "U$5") (pin "11") (pinfunction "MOSI_11") (pintype "input"))
    )
    (net (code "61") (name "Net-(C12-Pad1)") (class "Default")
      (node (ref "C12") (pin "1") (pinfunction "1_1") (pintype "passive"))
      (node (ref "R16") (pin "1") (pinfunction "1_1") (pintype "passive"))
      (node (ref "R17") (pin "2") (pinfunction "2_2") (pintype "passive"))
      (node (ref "U$6") (pin "V+") (pinfunction "V+_V+") (pintype "bidirectional"))
    )
    (net (code "62") (name "Net-(D1-A)") (class "Default")
      (node (ref "D1") (pin "1") (pinfunction "A_1") (pintype "passive"))
      (node (ref "D1") (pin "2") (pinfunction "A1_2") (pintype "passive"))
      (node (ref "IC2") (pin "1") (pinfunction "OUT_1") (pintype "output"))
    )
    (net (code "63") (name "Net-(D1-A2)") (class "Default")
      (node (ref "D1") (pin "3") (pinfunction "A2_3") (pintype "passive"))
      (node (ref "IC2") (pin "7") (pinfunction "OUT_7") (pintype "output"))
    )
    (net (code "64") (name "Net-(D1-A3)") (class "Default")
      (node (ref "D1") (pin "4") (pinfunction "A3_4") (pintype "passive"))
      (node (ref "IC2") (pin "8") (pinfunction "OUT_8") (pintype "output"))
    )
    (net (code "65") (name "Net-(D1-A4)") (class "Default")
      (node (ref "D1") (pin "5") (pinfunction "A4_5") (pintype "passive"))
      (node (ref "IC2") (pin "14") (pinfunction "OUT_14") (pintype "output"))
    )
    (net (code "66") (name "Net-(D1-C)") (class "Default")
      (node (ref "D1") (pin "16") (pinfunction "C4_16") (pintype "passive"))
      (node (ref "D1") (pin "17") (pinfunction "C3_17") (pintype "passive"))
      (node (ref "D1") (pin "18") (pinfunction "C2_18") (pintype "passive"))
      (node (ref "D1") (pin "19") (pinfunction "C1_19") (pintype "passive"))
      (node (ref "D1") (pin "20") (pinfunction "C_20") (pintype "passive"))
      (node (ref "JP1") (pin "2") (pinfunction "2_2") (pintype "passive"))
    )
    (net (code "67") (name "Net-(IC1-GND)") (class "Default")
      (node (ref "C1") (pin "1") (pinfunction "1_1") (pintype "passive"))
      (node (ref "C2") (pin "1") (pinfunction "1_1") (pintype "passive"))
      (node (ref "IC1") (pin "2") (pinfunction "GND_2") (pintype "passive"))
      (node (ref "JP10") (pin "1") (pinfunction "1_1") (pintype "passive"))
      (node (ref "JP8") (pin "2") (pinfunction "2_2") (pintype "passive"))
    )
    (net (code "68") (name "Net-(IC1-VI)") (class "Default")
      (node (ref "C1") (pin "2") (pinfunction "2_2") (pintype "passive"))
      (node (ref "IC1") (pin "1") (pinfunction "VI_1") (pintype "input"))
      (node (ref "JP10") (pin "2") (pinfunction "2_2") (pintype "passive"))
      (node (ref "JP9") (pin "2") (pinfunction "2_2") (pintype "passive"))
    )
    (net (code "69") (name "Net-(IC2A-+IN)") (class "Default")
      (node (ref "C3") (pin "1") (pinfunction "1_1") (pintype "passive"))
      (node (ref "C4") (pin "2") (pinfunction "2_2") (pintype "passive"))
      (node (ref "IC2") (pin "10") (pinfunction "+IN_10") (pintype "input"))
      (node (ref "IC2") (pin "12") (pinfunction "+IN_12") (pintype "input"))
      (node (ref "IC2") (pin "3") (pinfunction "+IN_3") (pintype "input"))
      (node (ref "IC2") (pin "5") (pinfunction "+IN_5") (pintype "input"))
      (node (ref "R1") (pin "2") (pinfunction "2_2") (pintype "passive"))
      (node (ref "R2") (pin "1") (pinfunction "1_1") (pintype "passive"))
    )
    (net (code "70") (name "Net-(IC2A--IN)") (class "Default")
      (node (ref "IC2") (pin "2") (pinfunction "-IN_2") (pintype "input"))
      (node (ref "R4") (pin "1") (pinfunction "1_1") (pintype "passive"))
      (node (ref "R5") (pin "2") (pinfunction "2_2") (pintype "passive"))
      (node (ref "R8") (pin "2") (pinfunction "2_2") (pintype "passive"))
    )
    (net (code "71") (name "Net-(IC2B--IN)") (class "Default")
      (node (ref "IC2") (pin "6") (pinfunction "-IN_6") (pintype "input"))
      (node (ref "R8") (pin "1") (pinfunction "1_1") (pintype "passive"))
      (node (ref "R9") (pin "2") (pinfunction "2_2") (pintype "passive"))
    )
    (net (code "72") (name "Net-(IC2C--IN)") (class "Default")
      (node (ref "IC2") (pin "9") (pinfunction "-IN_9") (pintype "input"))
      (node (ref "R10") (pin "2") (pinfunction "2_2") (pintype "passive"))
      (node (ref "R9") (pin "1") (pinfunction "1_1") (pintype "passive"))
    )
    (net (code "73") (name "Net-(IC2D--IN)") (class "Default")
      (node (ref "IC2") (pin "13") (pinfunction "-IN_13") (pintype "input"))
      (node (ref "R10") (pin "1") (pinfunction "1_1") (pintype "passive"))
      (node (ref "R11") (pin "2") (pinfunction "2_2") (pintype "passive"))
    )
    (net (code "74") (name "Net-(IC5A-C1+)") (class "Default")
      (node (ref "C5") (pin "2") (pinfunction "2_2") (pintype "passive"))
      (node (ref "IC5") (pin "1") (pinfunction "C1+_1") (pintype "bidirectional"))
    )
    (net (code "75") (name "Net-(IC5A-C1-)") (class "Default")
      (node (ref "C5") (pin "1") (pinfunction "1_1") (pintype "passive"))
      (node (ref "IC5") (pin "3") (pinfunction "C1-_3") (pintype "bidirectional"))
    )
    (net (code "76") (name "Net-(IC5A-C2+)") (class "Default")
      (node (ref "C6") (pin "2") (pinfunction "2_2") (pintype "passive"))
      (node (ref "IC5") (pin "4") (pinfunction "C2+_4") (pintype "bidirectional"))
    )
    (net (code "77") (name "Net-(IC5A-C2-)") (class "Default")
      (node (ref "C6") (pin "1") (pinfunction "1_1") (pintype "passive"))
      (node (ref "IC5") (pin "5") (pinfunction "C2-_5") (pintype "bidirectional"))
    )
    (net (code "78") (name "Net-(IC5A-V+)") (class "Default")
      (node (ref "C7") (pin "1") (pinfunction "1_1") (pintype "passive"))
      (node (ref "IC5") (pin "2") (pinfunction "V+_2") (pintype "bidirectional"))
    )
    (net (code "79") (name "Net-(IC5A-V-)") (class "Default")
      (node (ref "C8") (pin "2") (pinfunction "2_2") (pintype "passive"))
      (node (ref "IC5") (pin "6") (pinfunction "V-_6") (pintype "bidirectional"))
    )
    (net (code "80") (name "Net-(IC6-CBUS0)") (class "Default")
      (node (ref "IC6") (pin "23") (pinfunction "CBUS0_23") (pintype "bidirectional"))
      (node (ref "LED3") (pin "A") (pinfunction "A_A") (pintype "passive"))
    )
    (net (code "81") (name "Net-(IC6-CBUS1)") (class "Default")
      (node (ref "IC6") (pin "22") (pinfunction "CBUS1_22") (pintype "bidirectional"))
      (node (ref "LED4") (pin "A") (pinfunction "A_A") (pintype "passive"))
    )
    (net (code "82") (name "Net-(LED1-PadC)") (class "Default")
      (node (ref "LED1") (pin "C") (pinfunction "C_C") (pintype "passive"))
      (node (ref "R12") (pin "2") (pinfunction "2_2") (pintype "passive"))
    )
    (net (code "83") (name "Net-(LED2-PadC)") (class "Default")
      (node (ref "LED2") (pin "C") (pinfunction "C_C") (pintype "passive"))
      (node (ref "R13") (pin "2") (pinfunction "2_2") (pintype "passive"))
    )
    (net (code "84") (name "Net-(LED3-PadC)") (class "Default")
      (node (ref "LED3") (pin "C") (pinfunction "C_C") (pintype "passive"))
      (node (ref "R14") (pin "1") (pinfunction "1_1") (pintype "passive"))
    )
    (net (code "85") (name "Net-(LED4-PadC)") (class "Default")
      (node (ref "LED4") (pin "C") (pinfunction "C_C") (pintype "passive"))
      (node (ref "R15") (pin "1") (pinfunction "1_1") (pintype "passive"))
    )
    (net (code "86") (name "Net-(Q1-PadB)") (class "Default")
      (node (ref "Q1") (pin "B") (pinfunction "B_B") (pintype "passive"))
      (node (ref "R19") (pin "2") (pinfunction "2_2") (pintype "passive"))
    )
    (net (code "87") (name "Net-(Q2-PadB)") (class "Default")
      (node (ref "Q2") (pin "B") (pinfunction "B_B") (pintype "passive"))
      (node (ref "R20") (pin "2") (pinfunction "2_2") (pintype "passive"))
    )
    (net (code "88") (name "Net-(Q3-PadB)") (class "Default")
      (node (ref "Q3") (pin "B") (pinfunction "B_B") (pintype "passive"))
      (node (ref "R22") (pin "2") (pinfunction "2_2") (pintype "passive"))
    )
    (net (code "89") (name "Net-(Q4-PadB)") (class "Default")
      (node (ref "Q4") (pin "B") (pinfunction "B_B") (pintype "passive"))
      (node (ref "R21") (pin "2") (pinfunction "2_2") (pintype "passive"))
    )
    (net (code "90") (name "Net-(Q5-PadB)") (class "Default")
      (node (ref "Q5") (pin "B") (pinfunction "B_B") (pintype "passive"))
      (node (ref "R23") (pin "2") (pinfunction "2_2") (pintype "passive"))
    )
    (net (code "91") (name "Net-(Q6-PadB)") (class "Default")
      (node (ref "Q6") (pin "B") (pinfunction "B_B") (pintype "passive"))
      (node (ref "R24") (pin "2") (pinfunction "2_2") (pintype "passive"))
    )
    (net (code "92") (name "Net-(Q7-PadB)") (class "Default")
      (node (ref "Q7") (pin "B") (pinfunction "B_B") (pintype "passive"))
      (node (ref "R25") (pin "2") (pinfunction "2_2") (pintype "passive"))
    )
    (net (code "93") (name "Net-(Q8-PadB)") (class "Default")
      (node (ref "Q8") (pin "B") (pinfunction "B_B") (pintype "passive"))
      (node (ref "R26") (pin "2") (pinfunction "2_2") (pintype "passive"))
    )
    (net (code "94") (name "Net-(R3-Pad1)") (class "Default")
      (node (ref "R3") (pin "1") (pinfunction "1_1") (pintype "passive"))
      (node (ref "R4") (pin "2") (pinfunction "2_2") (pintype "passive"))
    )
    (net (code "95") (name "Net-(R6-Pad1)") (class "Default")
      (node (ref "R6") (pin "1") (pinfunction "1_1") (pintype "passive"))
      (node (ref "R7") (pin "2") (pinfunction "2_2") (pintype "passive"))
    )
    (net (code "96") (name "Net-(R11-Pad1)") (class "Default")
      (node (ref "R11") (pin "1") (pinfunction "1_1") (pintype "passive"))
      (node (ref "R5") (pin "1") (pinfunction "1_1") (pintype "passive"))
      (node (ref "R6") (pin "2") (pinfunction "2_2") (pintype "passive"))
    )
    (net (code "97") (name "PI1") (class "Default")
      (node (ref "IC3") (pin "18") (pinfunction "\\~{RESET}_18") (pintype "input"))
      (node (ref "IC3") (pin "9") (pinfunction "VDD_9") (pintype "power_in"))
      (node (ref "IC4") (pin "18") (pinfunction "\\~{RESET}_18") (pintype "input"))
      (node (ref "IC4") (pin "9") (pinfunction "VDD_9") (pintype "power_in"))
      (node (ref "U$2") (pin "2") (pinfunction "5-1_2") (pintype "bidirectional"))
      (node (ref "U$3") (pin "15") (pinfunction "VREF_15") (pintype "power_in"))
      (node (ref "U$3") (pin "16") (pinfunction "VDD_16") (pintype "power_in"))
      (node (ref "U$4") (pin "15") (pinfunction "VREF_15") (pintype "power_in"))
      (node (ref "U$4") (pin "16") (pinfunction "VDD_16") (pintype "power_in"))
      (node (ref "U$5") (pin "15") (pinfunction "VREF_15") (pintype "power_in"))
      (node (ref "U$5") (pin "16") (pinfunction "VDD_16") (pintype "power_in"))
    )
    (net (code "98") (name "PI2") (class "Default")
      (node (ref "C2") (pin "2") (pinfunction "2_2") (pintype "passive"))
      (node (ref "C7") (pin "2") (pinfunction "2_2") (pintype "passive"))
      (node (ref "C9") (pin "2") (pinfunction "2_2") (pintype "passive"))
      (node (ref "IC1") (pin "3") (pinfunction "VO_3") (pintype "passive"))
      (node (ref "R16") (pin "2") (pinfunction "2_2") (pintype "passive"))
      (node (ref "U$2") (pin "1") (pinfunction "3.31_1") (pintype "bidirectional"))
    )
    (net (code "99") (name "PI3") (class "Default")
      (node (ref "IC3") (pin "13") (pinfunction "SDA_13") (pintype "bidirectional"))
      (node (ref "IC4") (pin "13") (pinfunction "SDA_13") (pintype "bidirectional"))
      (node (ref "SV2") (pin "36") (pinfunction "36_36") (pintype "passive"))
      (node (ref "U$2") (pin "4") (pinfunction "5-2_4") (pintype "bidirectional"))
    )
    (net (code "100") (name "PI4") (class "Default")
      (node (ref "IC4") (pin "15") (pinfunction "A0_15") (pintype "input"))
      (node (ref "U$2") (pin "3") (pinfunction "SDA_3") (pintype "bidirectional"))
    )
    (net (code "101") (name "PI5") (class "Default")
      (node (ref "IC3") (pin "12") (pinfunction "SCL_12") (pintype "input"))
      (node (ref "IC4") (pin "12") (pinfunction "SCL_12") (pintype "input"))
      (node (ref "SV2") (pin "38") (pinfunction "38_38") (pintype "passive"))
      (node (ref "U$2") (pin "6") (pinfunction "GND1_6") (pintype "bidirectional"))
    )
    (net (code "102") (name "PI8") (class "Default")
      (node (ref "Q1") (pin "C") (pinfunction "C_C") (pintype "passive"))
      (node (ref "Q2") (pin "C") (pinfunction "C_C") (pintype "passive"))
      (node (ref "Q3") (pin "C") (pinfunction "C_C") (pintype "passive"))
      (node (ref "Q4") (pin "C") (pinfunction "C_C") (pintype "passive"))
      (node (ref "U$2") (pin "7") (pinfunction "4_7") (pintype "bidirectional"))
    )
    (net (code "103") (name "PI10") (class "Default")
      (node (ref "Q5") (pin "E") (pinfunction "E_E") (pintype "passive"))
      (node (ref "Q6") (pin "E") (pinfunction "E_E") (pintype "passive"))
      (node (ref "Q7") (pin "E") (pinfunction "E_E") (pintype "passive"))
      (node (ref "Q8") (pin "E") (pinfunction "E_E") (pintype "passive"))
      (node (ref "U$2") (pin "9") (pinfunction "GND2_9") (pintype "bidirectional"))
    )
    (net (code "104") (name "PI22") (class "Default")
      (node (ref "R17") (pin "1") (pinfunction "1_1") (pintype "passive"))
      (node (ref "U$2") (pin "16") (pinfunction "23_16") (pintype "bidirectional"))
      (node (ref "U$6") (pin "OUT") (pinfunction "OUT_OUT") (pintype "bidirectional"))
    )
    (net (code "105") (name "PWML") (class "Default")
      (node (ref "U$1") (pin "50") (pinfunction "50_50") (pintype "output"))
      (node (ref "U$1") (pin "50'") (pinfunction "50'_50'") (pintype "output"))
      (node (ref "U$2") (pin "39") (pinfunction "GND8_39") (pintype "bidirectional"))
    )
    (net (code "106") (name "PWMR") (class "Default")
      (node (ref "U$1") (pin "54") (pinfunction "54_54") (pintype "output"))
      (node (ref "U$1") (pin "54'") (pinfunction "54'_54'") (pintype "output"))
      (node (ref "U$2") (pin "32") (pinfunction "12_32") (pintype "bidirectional"))
    )
    (net (code "107") (name "R1") (class "Default")
      (node (ref "U$1") (pin "53") (pinfunction "53_53") (pintype "output"))
      (node (ref "U$1") (pin "53'") (pinfunction "53'_53'") (pintype "output"))
      (node (ref "U$2") (pin "34") (pinfunction "GND7_34") (pintype "bidirectional"))
    )
    (net (code "108") (name "R1OUT") (class "Default")
      (node (ref "IC5") (pin "12") (pinfunction "R1OUT_12") (pintype "output"))
    )
    (net (code "109") (name "R2") (class "Default")
      (node (ref "U$1") (pin "55") (pinfunction "55_55") (pintype "output"))
      (node (ref "U$1") (pin "55'") (pinfunction "55'_55'") (pintype "output"))
      (node (ref "U$2") (pin "30") (pinfunction "GND6_30") (pintype "bidirectional"))
    )
    (net (code "110") (name "RS") (class "Default")
      (node (ref "IC3") (pin "26") (pinfunction "GPA5_26") (pintype "bidirectional"))
      (node (ref "U$1") (pin "22") (pinfunction "22_22") (pintype "output"))
    )
    (net (code "111") (name "RXFT") (class "Default")
      (node (ref "IC6") (pin "5") (pinfunction "RXD_5") (pintype "input"))
      (node (ref "Q2") (pin "E") (pinfunction "E_E") (pintype "passive"))
    )
    (net (code "112") (name "RXP") (class "Default")
      (node (ref "Q1") (pin "E") (pinfunction "E_E") (pintype "passive"))
      (node (ref "SV2") (pin "8") (pinfunction "8_8") (pintype "passive"))
    )
    (net (code "113") (name "RXRS") (class "Default")
      (node (ref "IC5") (pin "14") (pinfunction "T1OUT_14") (pintype "output"))
      (node (ref "Q3") (pin "E") (pinfunction "E_E") (pintype "passive"))
      (node (ref "U$1") (pin "74") (pinfunction "74_74") (pintype "output"))
    )
    (net (code "114") (name "RXXB") (class "Default")
      (node (ref "Q4") (pin "E") (pinfunction "E_E") (pintype "passive"))
      (node (ref "U$1") (pin "13") (pinfunction "13_13") (pintype "output"))
    )
    (net (code "115") (name "RX_FT_EN") (class "Default")
      (node (ref "IC4") (pin "6") (pinfunction "GPB5_6") (pintype "bidirectional"))
      (node (ref "R20") (pin "1") (pinfunction "1_1") (pintype "passive"))
    )
    (net (code "116") (name "RX_P_EN") (class "Default")
      (node (ref "IC4") (pin "5") (pinfunction "GPB4_5") (pintype "bidirectional"))
      (node (ref "R19") (pin "1") (pinfunction "1_1") (pintype "passive"))
    )
    (net (code "117") (name "RX_RS_EN") (class "Default")
      (node (ref "IC4") (pin "8") (pinfunction "GPB7_8") (pintype "bidirectional"))
      (node (ref "R22") (pin "1") (pinfunction "1_1") (pintype "passive"))
    )
    (net (code "118") (name "RX_XB_EN") (class "Default")
      (node (ref "IC4") (pin "7") (pinfunction "GPB6_7") (pintype "bidirectional"))
      (node (ref "R21") (pin "1") (pinfunction "1_1") (pintype "passive"))
    )
    (net (code "119") (name "SERVO") (class "Default")
      (node (ref "C15") (pin "2") (pinfunction "2_2") (pintype "passive"))
      (node (ref "C16") (pin "2") (pinfunction "2_2") (pintype "passive"))
      (node (ref "IC7") (pin "2") (pinfunction "OUT_2") (pintype "passive"))
      (node (ref "U$7") (pin "1") (pinfunction "1_1") (pintype "bidirectional"))
      (node (ref "U$7") (pin "1\"") (pinfunction "1\"_1\"") (pintype "bidirectional"))
      (node (ref "U$7") (pin "1'") (pinfunction "1'_1'") (pintype "bidirectional"))
    )
    (net (code "120") (name "SERVO1") (class "Default")
      (node (ref "U$2") (pin "11") (pinfunction "17_11") (pintype "bidirectional"))
      (node (ref "U$7") (pin "2") (pinfunction "2_2") (pintype "bidirectional"))
    )
    (net (code "121") (name "SERVO2") (class "Default")
      (node (ref "U$2") (pin "15") (pinfunction "22_15") (pintype "bidirectional"))
      (node (ref "U$7") (pin "2'") (pinfunction "2'_2'") (pintype "bidirectional"))
    )
    (net (code "122") (name "SERVO3") (class "Default")
      (node (ref "U$2") (pin "17") (pinfunction "3.3-2_17") (pintype "bidirectional"))
      (node (ref "U$7") (pin "2\"") (pinfunction "2\"_2\"") (pintype "bidirectional"))
    )
    (net (code "123") (name "SH1") (class "Default")
      (node (ref "U$1") (pin "11") (pinfunction "11_11") (pintype "output"))
      (node (ref "U$4") (pin "1") (pinfunction "CH0_1") (pintype "input"))
    )
    (net (code "124") (name "SH2") (class "Default")
      (node (ref "U$1") (pin "15") (pinfunction "15_15") (pintype "output"))
      (node (ref "U$4") (pin "2") (pinfunction "CH1_2") (pintype "input"))
    )
    (net (code "125") (name "SH3") (class "Default")
      (node (ref "U$1") (pin "41") (pinfunction "41_41") (pintype "output"))
      (node (ref "U$4") (pin "3") (pinfunction "CH2_3") (pintype "input"))
    )
    (net (code "126") (name "SH4") (class "Default")
      (node (ref "U$1") (pin "44") (pinfunction "44_44") (pintype "output"))
      (node (ref "U$4") (pin "4") (pinfunction "CH3_4") (pintype "input"))
    )
    (net (code "127") (name "SH5") (class "Default")
      (node (ref "U$1") (pin "45") (pinfunction "45_45") (pintype "output"))
      (node (ref "U$4") (pin "5") (pinfunction "CH4_5") (pintype "input"))
    )
    (net (code "128") (name "SPICLK") (class "Default")
      (node (ref "SV2") (pin "37") (pinfunction "37_37") (pintype "passive"))
      (node (ref "U$2") (pin "24") (pinfunction "CE0_24") (pintype "bidirectional"))
      (node (ref "U$3") (pin "13") (pinfunction "SCK_13") (pintype "input"))
      (node (ref "U$4") (pin "13") (pinfunction "SCK_13") (pintype "input"))
      (node (ref "U$5") (pin "13") (pinfunction "SCK_13") (pintype "input"))
    )
    (net (code "129") (name "T1IN") (class "Default")
      (node (ref "IC5") (pin "11") (pinfunction "T1IN_11") (pintype "input"))
    )
    (net (code "130") (name "TXFT") (class "Default")
      (node (ref "IC6") (pin "1") (pinfunction "TXD_1") (pintype "output"))
      (node (ref "Q6") (pin "C") (pinfunction "C_C") (pintype "passive"))
    )
    (net (code "131") (name "TXP") (class "Default")
      (node (ref "Q5") (pin "C") (pinfunction "C_C") (pintype "passive"))
      (node (ref "SV2") (pin "7") (pinfunction "7_7") (pintype "passive"))
    )
    (net (code "132") (name "TXRS") (class "Default")
      (node (ref "IC5") (pin "13") (pinfunction "R1IN_13") (pintype "input"))
      (node (ref "Q8") (pin "C") (pinfunction "C_C") (pintype "passive"))
      (node (ref "U$1") (pin "73") (pinfunction "73_73") (pintype "output"))
    )
    (net (code "133") (name "TXXB") (class "Default")
      (node (ref "Q7") (pin "C") (pinfunction "C_C") (pintype "passive"))
      (node (ref "U$1") (pin "14") (pinfunction "14_14") (pintype "output"))
    )
    (net (code "134") (name "TX_FT_EN") (class "Default")
      (node (ref "IC4") (pin "2") (pinfunction "GPB1_2") (pintype "bidirectional"))
      (node (ref "R24") (pin "1") (pinfunction "1_1") (pintype "passive"))
    )
    (net (code "135") (name "TX_P_EN") (class "Default")
      (node (ref "IC4") (pin "1") (pinfunction "GPB0_1") (pintype "bidirectional"))
      (node (ref "R23") (pin "1") (pinfunction "1_1") (pintype "passive"))
    )
    (net (code "136") (name "TX_RS_EN") (class "Default")
      (node (ref "IC4") (pin "4") (pinfunction "GPB3_4") (pintype "bidirectional"))
      (node (ref "R26") (pin "1") (pinfunction "1_1") (pintype "passive"))
    )
    (net (code "137") (name "TX_XB_EN") (class "Default")
      (node (ref "IC4") (pin "3") (pinfunction "GPB2_3") (pintype "bidirectional"))
      (node (ref "R25") (pin "1") (pinfunction "1_1") (pintype "passive"))
    )
    (net (code "138") (name "WL1") (class "Default")
      (node (ref "U$1") (pin "30") (pinfunction "30_30") (pintype "output"))
      (node (ref "U$4") (pin "6") (pinfunction "CH5_6") (pintype "input"))
    )
    (net (code "139") (name "WL2") (class "Default")
      (node (ref "U$1") (pin "31") (pinfunction "31_31") (pintype "output"))
      (node (ref "U$4") (pin "7") (pinfunction "CH6_7") (pintype "input"))
    )
    (net (code "140") (name "WL3") (class "Default")
      (node (ref "U$1") (pin "32") (pinfunction "32_32") (pintype "output"))
      (node (ref "U$4") (pin "8") (pinfunction "CH7_8") (pintype "input"))
    )
    (net (code "141") (name "WL4") (class "Default")
      (node (ref "SV1") (pin "1") (pinfunction "1_1") (pintype "passive"))
      (node (ref "U$1") (pin "36") (pinfunction "36_36") (pintype "output"))
    )
    (net (code "142") (name "WL5") (class "Default")
      (node (ref "SV1") (pin "2") (pinfunction "2_2") (pintype "passive"))
      (node (ref "U$1") (pin "37") (pinfunction "37_37") (pintype "output"))
    )
    (net (code "143") (name "WL6") (class "Default")
      (node (ref "SV1") (pin "3") (pinfunction "3_3") (pintype "passive"))
      (node (ref "U$1") (pin "38") (pinfunction "38_38") (pintype "output"))
    )
    (net (code "144") (name "WL7") (class "Default")
      (node (ref "SV1") (pin "4") (pinfunction "4_4") (pintype "passive"))
      (node (ref "U$1") (pin "39") (pinfunction "39_39") (pintype "output"))
    )
    (net (code "145") (name "unconnected-(IC3-GPA6-Pad27)") (class "Default")
      (node (ref "IC3") (pin "27") (pinfunction "GPA6_27") (pintype "bidirectional"))
    )
    (net (code "146") (name "unconnected-(IC3-GPA7-Pad28)") (class "Default")
      (node (ref "IC3") (pin "28") (pinfunction "GPA7_28") (pintype "bidirectional"))
    )
    (net (code "147") (name "unconnected-(IC3-INTA-Pad20)") (class "Default")
      (node (ref "IC3") (pin "20") (pinfunction "INTA_20") (pintype "output"))
    )
    (net (code "148") (name "unconnected-(IC3-INTB-Pad19)") (class "Default")
      (node (ref "IC3") (pin "19") (pinfunction "INTB_19") (pintype "output"))
    )
    (net (code "149") (name "unconnected-(IC4-INTA-Pad20)") (class "Default")
      (node (ref "IC4") (pin "20") (pinfunction "INTA_20") (pintype "output"))
    )
    (net (code "150") (name "unconnected-(IC4-INTB-Pad19)") (class "Default")
      (node (ref "IC4") (pin "19") (pinfunction "INTB_19") (pintype "output"))
    )
    (net (code "151") (name "unconnected-(IC5A-R2IN-Pad8)") (class "Default")
      (node (ref "IC5") (pin "8") (pinfunction "R2IN_8") (pintype "input"))
    )
    (net (code "152") (name "unconnected-(IC5A-R2OUT-Pad9)") (class "Default")
      (node (ref "IC5") (pin "9") (pinfunction "R2OUT_9") (pintype "output"))
    )
    (net (code "153") (name "unconnected-(IC5A-T2IN-Pad10)") (class "Default")
      (node (ref "IC5") (pin "10") (pinfunction "T2IN_10") (pintype "input"))
    )
    (net (code "154") (name "unconnected-(IC5A-T2OUT-Pad7)") (class "Default")
      (node (ref "IC5") (pin "7") (pinfunction "T2OUT_7") (pintype "output"))
    )
    (net (code "155") (name "unconnected-(IC6-3V3OUT-Pad17)") (class "Default")
      (node (ref "IC6") (pin "17") (pinfunction "3V3OUT_17") (pintype "output"))
    )
    (net (code "156") (name "unconnected-(IC6-CBUS2-Pad13)") (class "Default")
      (node (ref "IC6") (pin "13") (pinfunction "CBUS2_13") (pintype "bidirectional"))
    )
    (net (code "157") (name "unconnected-(IC6-CBUS3-Pad14)") (class "Default")
      (node (ref "IC6") (pin "14") (pinfunction "CBUS3_14") (pintype "bidirectional"))
    )
    (net (code "158") (name "unconnected-(IC6-CBUS4-Pad12)") (class "Default")
      (node (ref "IC6") (pin "12") (pinfunction "CBUS4_12") (pintype "bidirectional"))
    )
    (net (code "159") (name "unconnected-(IC6-OSCI-Pad27)") (class "Default")
      (node (ref "IC6") (pin "27") (pinfunction "OSCI_27") (pintype "input"))
    )
    (net (code "160") (name "unconnected-(IC6-OSCO-Pad28)") (class "Default")
      (node (ref "IC6") (pin "28") (pinfunction "OSCO_28") (pintype "output"))
    )
    (net (code "161") (name "unconnected-(IC6-~{CTS}-Pad11)") (class "Default")
      (node (ref "IC6") (pin "11") (pinfunction "~{CTS}_11") (pintype "input"))
    )
    (net (code "162") (name "unconnected-(IC6-~{DCD}-Pad10)") (class "Default")
      (node (ref "IC6") (pin "10") (pinfunction "~{DCD}_10") (pintype "input"))
    )
    (net (code "163") (name "unconnected-(IC6-~{DSR}-Pad9)") (class "Default")
      (node (ref "IC6") (pin "9") (pinfunction "~{DSR}_9") (pintype "input"))
    )
    (net (code "164") (name "unconnected-(IC6-~{DTR}-Pad2)") (class "Default")
      (node (ref "IC6") (pin "2") (pinfunction "~{DTR}_2") (pintype "output"))
    )
    (net (code "165") (name "unconnected-(IC6-~{RESET}-Pad19)") (class "Default")
      (node (ref "IC6") (pin "19") (pinfunction "~{RESET}_19") (pintype "input"))
    )
    (net (code "166") (name "unconnected-(IC6-~{RI}-Pad6)") (class "Default")
      (node (ref "IC6") (pin "6") (pinfunction "~{RI}_6") (pintype "input"))
    )
    (net (code "167") (name "unconnected-(IC6-~{RTS}-Pad3)") (class "Default")
      (node (ref "IC6") (pin "3") (pinfunction "~{RTS}_3") (pintype "output"))
    )
    (net (code "168") (name "unconnected-(IC7-OUT1-PadTAB)") (class "Default")
      (node (ref "IC7") (pin "TAB") (pinfunction "OUT1_TAB") (pintype "passive"))
    )
    (net (code "169") (name "unconnected-(SV1-Pad5)") (class "Default")
      (node (ref "SV1") (pin "5") (pinfunction "5_5") (pintype "passive"))
    )
    (net (code "170") (name "unconnected-(SV2-Pad17)") (class "Default")
      (node (ref "SV2") (pin "17") (pinfunction "17_17") (pintype "passive"))
    )
    (net (code "171") (name "unconnected-(SV2-Pad19)") (class "Default")
      (node (ref "SV2") (pin "19") (pinfunction "19_19") (pintype "passive"))
    )
    (net (code "172") (name "unconnected-(SV2-Pad21)") (class "Default")
      (node (ref "SV2") (pin "21") (pinfunction "21_21") (pintype "passive"))
    )
    (net (code "173") (name "unconnected-(SV2-Pad23)") (class "Default")
      (node (ref "SV2") (pin "23") (pinfunction "23_23") (pintype "passive"))
    )
    (net (code "174") (name "unconnected-(SV2-Pad25)") (class "Default")
      (node (ref "SV2") (pin "25") (pinfunction "25_25") (pintype "passive"))
    )
    (net (code "175") (name "unconnected-(SV2-Pad27)") (class "Default")
      (node (ref "SV2") (pin "27") (pinfunction "27_27") (pintype "passive"))
    )
    (net (code "176") (name "unconnected-(SV2-Pad29)") (class "Default")
      (node (ref "SV2") (pin "29") (pinfunction "29_29") (pintype "passive"))
    )
    (net (code "177") (name "unconnected-(SV2-Pad31)") (class "Default")
      (node (ref "SV2") (pin "31") (pinfunction "31_31") (pintype "passive"))
    )
    (net (code "178") (name "unconnected-(SV2-Pad34)") (class "Default")
      (node (ref "SV2") (pin "34") (pinfunction "34_34") (pintype "passive"))
    )
    (net (code "179") (name "unconnected-(U$1-Pad1')") (class "Default")
      (node (ref "U$1") (pin "1'") (pinfunction "1'_1'") (pintype "output"))
    )
    (net (code "180") (name "unconnected-(U$1-Pad1)") (class "Default")
      (node (ref "U$1") (pin "1") (pinfunction "1_1") (pintype "output"))
    )
    (net (code "181") (name "unconnected-(U$1-Pad2')") (class "Default")
      (node (ref "U$1") (pin "2'") (pinfunction "2'_2'") (pintype "output"))
    )
    (net (code "182") (name "unconnected-(U$1-Pad3')") (class "Default")
      (node (ref "U$1") (pin "3'") (pinfunction "3'_3'") (pintype "output"))
    )
    (net (code "183") (name "unconnected-(U$1-Pad4')") (class "Default")
      (node (ref "U$1") (pin "4'") (pinfunction "4'_4'") (pintype "output"))
    )
    (net (code "184") (name "unconnected-(U$1-Pad5')") (class "Default")
      (node (ref "U$1") (pin "5'") (pinfunction "5'_5'") (pintype "output"))
    )
    (net (code "185") (name "unconnected-(U$1-Pad6')") (class "Default")
      (node (ref "U$1") (pin "6'") (pinfunction "6'_6'") (pintype "output"))
    )
    (net (code "186") (name "unconnected-(U$1-Pad7A)") (class "Default")
      (node (ref "U$1") (pin "7A") (pinfunction "7A_7A") (pintype "output"))
    )
    (net (code "187") (name "unconnected-(U$1-Pad8)") (class "Default")
      (node (ref "U$1") (pin "8") (pinfunction "8_8") (pintype "output"))
    )
    (net (code "188") (name "unconnected-(U$1-Pad8A)") (class "Default")
      (node (ref "U$1") (pin "8A") (pinfunction "8A_8A") (pintype "output"))
    )
    (net (code "189") (name "unconnected-(U$1-Pad9A)") (class "Default")
      (node (ref "U$1") (pin "9A") (pinfunction "9A_9A") (pintype "output"))
    )
    (net (code "190") (name "unconnected-(U$1-Pad10A)") (class "Default")
      (node (ref "U$1") (pin "10A") (pinfunction "10A_10A") (pintype "output"))
    )
    (net (code "191") (name "unconnected-(U$1-Pad11')") (class "Default")
      (node (ref "U$1") (pin "11'") (pinfunction "11'_11'") (pintype "output"))
    )
    (net (code "192") (name "unconnected-(U$1-Pad12')") (class "Default")
      (node (ref "U$1") (pin "12'") (pinfunction "12'_12'") (pintype "output"))
    )
    (net (code "193") (name "unconnected-(U$1-Pad13')") (class "Default")
      (node (ref "U$1") (pin "13'") (pinfunction "13'_13'") (pintype "output"))
    )
    (net (code "194") (name "unconnected-(U$1-Pad14')") (class "Default")
      (node (ref "U$1") (pin "14'") (pinfunction "14'_14'") (pintype "output"))
    )
    (net (code "195") (name "unconnected-(U$1-Pad15')") (class "Default")
      (node (ref "U$1") (pin "15'") (pinfunction "15'_15'") (pintype "output"))
    )
    (net (code "196") (name "unconnected-(U$1-Pad16')") (class "Default")
      (node (ref "U$1") (pin "16'") (pinfunction "16'_16'") (pintype "output"))
    )
    (net (code "197") (name "unconnected-(U$1-Pad17A)") (class "Default")
      (node (ref "U$1") (pin "17A") (pinfunction "17A_17A") (pintype "output"))
    )
    (net (code "198") (name "unconnected-(U$1-Pad17B)") (class "Default")
      (node (ref "U$1") (pin "17B") (pinfunction "17B_17B") (pintype "output"))
    )
    (net (code "199") (name "unconnected-(U$1-Pad18')") (class "Default")
      (node (ref "U$1") (pin "18'") (pinfunction "18'_18'") (pintype "output"))
    )
    (net (code "200") (name "unconnected-(U$1-Pad18)") (class "Default")
      (node (ref "U$1") (pin "18") (pinfunction "18_18") (pintype "output"))
    )
    (net (code "201") (name "unconnected-(U$1-Pad19')") (class "Default")
      (node (ref "U$1") (pin "19'") (pinfunction "19'_19'") (pintype "output"))
    )
    (net (code "202") (name "unconnected-(U$1-Pad19)") (class "Default")
      (node (ref "U$1") (pin "19") (pinfunction "19_19") (pintype "output"))
    )
    (net (code "203") (name "unconnected-(U$1-Pad20)") (class "Default")
      (node (ref "U$1") (pin "20") (pinfunction "20_20") (pintype "output"))
    )
    (net (code "204") (name "unconnected-(U$1-Pad20A)") (class "Default")
      (node (ref "U$1") (pin "20A") (pinfunction "20A_20A") (pintype "output"))
    )
    (net (code "205") (name "unconnected-(U$1-Pad21)") (class "Default")
      (node (ref "U$1") (pin "21") (pinfunction "21_21") (pintype "output"))
    )
    (net (code "206") (name "unconnected-(U$1-Pad21A)") (class "Default")
      (node (ref "U$1") (pin "21A") (pinfunction "21A_21A") (pintype "output"))
    )
    (net (code "207") (name "unconnected-(U$1-Pad22')") (class "Default")
      (node (ref "U$1") (pin "22'") (pinfunction "22'_22'") (pintype "output"))
    )
    (net (code "208") (name "unconnected-(U$1-Pad23')") (class "Default")
      (node (ref "U$1") (pin "23'") (pinfunction "23'_23'") (pintype "output"))
    )
    (net (code "209") (name "unconnected-(U$1-Pad24')") (class "Default")
      (node (ref "U$1") (pin "24'") (pinfunction "24'_24'") (pintype "output"))
    )
    (net (code "210") (name "unconnected-(U$1-Pad25')") (class "Default")
      (node (ref "U$1") (pin "25'") (pinfunction "25'_25'") (pintype "output"))
    )
    (net (code "211") (name "unconnected-(U$1-Pad26')") (class "Default")
      (node (ref "U$1") (pin "26'") (pinfunction "26'_26'") (pintype "output"))
    )
    (net (code "212") (name "unconnected-(U$1-Pad27')") (class "Default")
      (node (ref "U$1") (pin "27'") (pinfunction "27'_27'") (pintype "output"))
    )
    (net (code "213") (name "unconnected-(U$1-Pad28')") (class "Default")
      (node (ref "U$1") (pin "28'") (pinfunction "28'_28'") (pintype "output"))
    )
    (net (code "214") (name "unconnected-(U$1-Pad29')") (class "Default")
      (node (ref "U$1") (pin "29'") (pinfunction "29'_29'") (pintype "output"))
    )
    (net (code "215") (name "unconnected-(U$1-Pad30')") (class "Default")
      (node (ref "U$1") (pin "30'") (pinfunction "30'_30'") (pintype "output"))
    )
    (net (code "216") (name "unconnected-(U$1-Pad31')") (class "Default")
      (node (ref "U$1") (pin "31'") (pinfunction "31'_31'") (pintype "output"))
    )
    (net (code "217") (name "unconnected-(U$1-Pad32')") (class "Default")
      (node (ref "U$1") (pin "32'") (pinfunction "32'_32'") (pintype "output"))
    )
    (net (code "218") (name "unconnected-(U$1-Pad33')") (class "Default")
      (node (ref "U$1") (pin "33'") (pinfunction "33'_33'") (pintype "output"))
    )
    (net (code "219") (name "unconnected-(U$1-Pad34')") (class "Default")
      (node (ref "U$1") (pin "34'") (pinfunction "34'_34'") (pintype "output"))
    )
    (net (code "220") (name "unconnected-(U$1-Pad35)") (class "Default")
      (node (ref "U$1") (pin "35") (pinfunction "35_35") (pintype "output"))
    )
    (net (code "221") (name "unconnected-(U$1-Pad35A)") (class "Default")
      (node (ref "U$1") (pin "35A") (pinfunction "35A_35A") (pintype "output"))
    )
    (net (code "222") (name "unconnected-(U$1-Pad36')") (class "Default")
      (node (ref "U$1") (pin "36'") (pinfunction "36'_36'") (pintype "output"))
    )
    (net (code "223") (name "unconnected-(U$1-Pad37')") (class "Default")
      (node (ref "U$1") (pin "37'") (pinfunction "37'_37'") (pintype "output"))
    )
    (net (code "224") (name "unconnected-(U$1-Pad38')") (class "Default")
      (node (ref "U$1") (pin "38'") (pinfunction "38'_38'") (pintype "output"))
    )
    (net (code "225") (name "unconnected-(U$1-Pad39')") (class "Default")
      (node (ref "U$1") (pin "39'") (pinfunction "39'_39'") (pintype "output"))
    )
    (net (code "226") (name "unconnected-(U$1-Pad40')") (class "Default")
      (node (ref "U$1") (pin "40'") (pinfunction "40'_40'") (pintype "output"))
    )
    (net (code "227") (name "unconnected-(U$1-Pad41')") (class "Default")
      (node (ref "U$1") (pin "41'") (pinfunction "41'_41'") (pintype "output"))
    )
    (net (code "228") (name "unconnected-(U$1-Pad42')") (class "Default")
      (node (ref "U$1") (pin "42'") (pinfunction "42'_42'") (pintype "output"))
    )
    (net (code "229") (name "unconnected-(U$1-Pad43')") (class "Default")
      (node (ref "U$1") (pin "43'") (pinfunction "43'_43'") (pintype "output"))
    )
    (net (code "230") (name "unconnected-(U$1-Pad44')") (class "Default")
      (node (ref "U$1") (pin "44'") (pinfunction "44'_44'") (pintype "output"))
    )
    (net (code "231") (name "unconnected-(U$1-Pad45')") (class "Default")
      (node (ref "U$1") (pin "45'") (pinfunction "45'_45'") (pintype "output"))
    )
    (net (code "232") (name "unconnected-(U$1-Pad46')") (class "Default")
      (node (ref "U$1") (pin "46'") (pinfunction "46'_46'") (pintype "output"))
    )
    (net (code "233") (name "unconnected-(U$1-Pad47')") (class "Default")
      (node (ref "U$1") (pin "47'") (pinfunction "47'_47'") (pintype "output"))
    )
    (net (code "234") (name "unconnected-(U$1-Pad47)") (class "Default")
      (node (ref "U$1") (pin "47") (pinfunction "47_47") (pintype "output"))
    )
    (net (code "235") (name "unconnected-(U$1-Pad48')") (class "Default")
      (node (ref "U$1") (pin "48'") (pinfunction "48'_48'") (pintype "output"))
    )
    (net (code "236") (name "unconnected-(U$1-Pad48)") (class "Default")
      (node (ref "U$1") (pin "48") (pinfunction "48_48") (pintype "output"))
    )
    (net (code "237") (name "unconnected-(U$1-Pad49')") (class "Default")
      (node (ref "U$1") (pin "49'") (pinfunction "49'_49'") (pintype "output"))
    )
    (net (code "238") (name "unconnected-(U$1-Pad49)") (class "Default")
      (node (ref "U$1") (pin "49") (pinfunction "49_49") (pintype "output"))
    )
    (net (code "239") (name "unconnected-(U$1-Pad57)") (class "Default")
      (node (ref "U$1") (pin "57") (pinfunction "57_57") (pintype "output"))
    )
    (net (code "240") (name "unconnected-(U$1-Pad57A)") (class "Default")
      (node (ref "U$1") (pin "57A") (pinfunction "57A_57A") (pintype "output"))
    )
    (net (code "241") (name "unconnected-(U$1-Pad58)") (class "Default")
      (node (ref "U$1") (pin "58") (pinfunction "58_58") (pintype "output"))
    )
    (net (code "242") (name "unconnected-(U$1-Pad58A)") (class "Default")
      (node (ref "U$1") (pin "58A") (pinfunction "58A_58A") (pintype "output"))
    )
    (net (code "243") (name "unconnected-(U$1-Pad59)") (class "Default")
      (node (ref "U$1") (pin "59") (pinfunction "59_59") (pintype "output"))
    )
    (net (code "244") (name "unconnected-(U$1-Pad59A)") (class "Default")
      (node (ref "U$1") (pin "59A") (pinfunction "59A_59A") (pintype "output"))
    )
    (net (code "245") (name "unconnected-(U$1-Pad60)") (class "Default")
      (node (ref "U$1") (pin "60") (pinfunction "60_60") (pintype "output"))
    )
    (net (code "246") (name "unconnected-(U$1-Pad60A)") (class "Default")
      (node (ref "U$1") (pin "60A") (pinfunction "60A_60A") (pintype "output"))
    )
    (net (code "247") (name "unconnected-(U$1-Pad61')") (class "Default")
      (node (ref "U$1") (pin "61'") (pinfunction "61'_61'") (pintype "output"))
    )
    (net (code "248") (name "unconnected-(U$1-Pad61)") (class "Default")
      (node (ref "U$1") (pin "61") (pinfunction "61_61") (pintype "output"))
    )
    (net (code "249") (name "unconnected-(U$1-Pad62')") (class "Default")
      (node (ref "U$1") (pin "62'") (pinfunction "62'_62'") (pintype "output"))
    )
    (net (code "250") (name "unconnected-(U$1-Pad63')") (class "Default")
      (node (ref "U$1") (pin "63'") (pinfunction "63'_63'") (pintype "output"))
    )
    (net (code "251") (name "unconnected-(U$1-Pad64')") (class "Default")
      (node (ref "U$1") (pin "64'") (pinfunction "64'_64'") (pintype "output"))
    )
    (net (code "252") (name "unconnected-(U$1-Pad64)") (class "Default")
      (node (ref "U$1") (pin "64") (pinfunction "64_64") (pintype "output"))
    )
    (net (code "253") (name "unconnected-(U$1-Pad65')") (class "Default")
      (node (ref "U$1") (pin "65'") (pinfunction "65'_65'") (pintype "output"))
    )
    (net (code "254") (name "unconnected-(U$1-Pad65)") (class "Default")
      (node (ref "U$1") (pin "65") (pinfunction "65_65") (pintype "output"))
    )
    (net (code "255") (name "unconnected-(U$1-Pad66')") (class "Default")
      (node (ref "U$1") (pin "66'") (pinfunction "66'_66'") (pintype "output"))
    )
    (net (code "256") (name "unconnected-(U$1-Pad66)") (class "Default")
      (node (ref "U$1") (pin "66") (pinfunction "66_66") (pintype "output"))
    )
    (net (code "257") (name "unconnected-(U$1-Pad67')") (class "Default")
      (node (ref "U$1") (pin "67'") (pinfunction "67'_67'") (pintype "output"))
    )
    (net (code "258") (name "unconnected-(U$1-Pad67)") (class "Default")
      (node (ref "U$1") (pin "67") (pinfunction "67_67") (pintype "output"))
    )
    (net (code "259") (name "unconnected-(U$1-Pad68')") (class "Default")
      (node (ref "U$1") (pin "68'") (pinfunction "68'_68'") (pintype "output"))
    )
    (net (code "260") (name "unconnected-(U$1-Pad68)") (class "Default")
      (node (ref "U$1") (pin "68") (pinfunction "68_68") (pintype "output"))
    )
    (net (code "261") (name "unconnected-(U$1-Pad69')") (class "Default")
      (node (ref "U$1") (pin "69'") (pinfunction "69'_69'") (pintype "output"))
    )
    (net (code "262") (name "unconnected-(U$1-Pad70')") (class "Default")
      (node (ref "U$1") (pin "70'") (pinfunction "70'_70'") (pintype "output"))
    )
    (net (code "263") (name "unconnected-(U$1-Pad71')") (class "Default")
      (node (ref "U$1") (pin "71'") (pinfunction "71'_71'") (pintype "output"))
    )
    (net (code "264") (name "unconnected-(U$1-Pad72')") (class "Default")
      (node (ref "U$1") (pin "72'") (pinfunction "72'_72'") (pintype "output"))
    )
    (net (code "265") (name "unconnected-(U$1-Pad72)") (class "Default")
      (node (ref "U$1") (pin "72") (pinfunction "72_72") (pintype "output"))
    )
    (net (code "266") (name "unconnected-(U$1-Pad73')") (class "Default")
      (node (ref "U$1") (pin "73'") (pinfunction "73'_73'") (pintype "output"))
    )
    (net (code "267") (name "unconnected-(U$1-Pad74')") (class "Default")
      (node (ref "U$1") (pin "74'") (pinfunction "74'_74'") (pintype "output"))
    )
    (net (code "268") (name "unconnected-(U$2-6-Pad31)") (class "Default")
      (node (ref "U$2") (pin "31") (pinfunction "6_31") (pintype "bidirectional"))
    )
    (net (code "269") (name "unconnected-(U$2-24-Pad18)") (class "Default")
      (node (ref "U$2") (pin "18") (pinfunction "24_18") (pintype "bidirectional"))
    )
    (net (code "270") (name "unconnected-(U$2-CE1-Pad26)") (class "Default")
      (node (ref "U$2") (pin "26") (pinfunction "CE1_26") (pintype "bidirectional"))
    )
    (net (code "271") (name "unconnected-(U$2-TX-Pad8)") (class "Default")
      (node (ref "U$2") (pin "8") (pinfunction "TX_8") (pintype "bidirectional"))
    )
  )
)
